# 24Vto5Vat1A-R1.net
KiCad netlist of a schematic drawn in Altium Designer
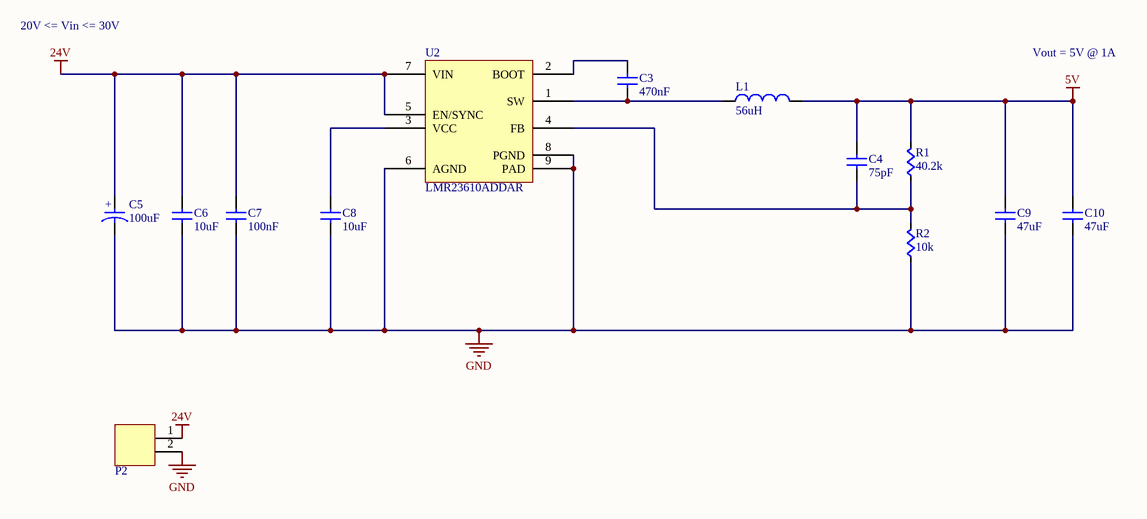
[diagram p0: 24Vto5Vat1A-R1.SchDoc]

(export (version "E")
  (design (tool "Eeschema 10.0.6"))
  (components
    (comp (ref "C3")
      (value "470nF")
      (footprint "CAPC0603")
      (fields (field (name "Comment") "Cap"))
      (libsource (lib "Passives") (part "Cap"))
    )
    (comp (ref "C4")
      (value "75pF")
      (footprint "CAPC0603")
      (fields (field (name "Comment") "Cap"))
      (libsource (lib "Passives") (part "Cap"))
    )
    (comp (ref "C5")
      (value "100uF")
      (footprint "EEHZA1H101P")
      (description "CAP ALUM POLY HYB 100UF 50V SMD")
      (fields (field (name "VOLTAGE") "50V") (field (name "TOLERANCE") "20%"))
      (libsource (lib "SubjuGator8") (part "EEHZA1H101P"))
    )
    (comp (ref "C6")
      (value "10uF")
      (footprint "CAP1210")
      (fields (field (name "Comment") "Cap"))
      (libsource (lib "Passives") (part "Cap"))
    )
    (comp (ref "C7")
      (value "100nF")
      (footprint "CAPC0603")
      (fields (field (name "Comment") "Cap"))
      (libsource (lib "Passives") (part "Cap"))
    )
    (comp (ref "C8")
      (value "10uF")
      (footprint "CAPC0603")
      (fields (field (name "Comment") "Cap"))
      (libsource (lib "Passives") (part "Cap"))
    )
    (comp (ref "C9")
      (value "47uF")
      (footprint "CAP1210")
      (fields (field (name "Comment") "Cap"))
      (libsource (lib "SubjuGator8") (part "Cap"))
    )
    (comp (ref "C10")
      (value "47uF")
      (footprint "CAP1210")
      (fields (field (name "Comment") "Cap"))
      (libsource (lib "SubjuGator8") (part "Cap"))
    )
    (comp (ref "L1")
      (value "56uH")
      (footprint "MSS1048-563MLB")
      (description "FIXED IND 56UH 1.7A 126 MOHM")
      (fields (field (name "Comment") "MSS1048-563MLB"))
      (libsource (lib "SubjuGator8") (part "MSS1048-563MLB"))
    )
    (comp (ref "P2")
      (value "2-pin Horz Sherlock")
      (footprint "MOLEX-HDR-1X2-SHERLOCK-HORZ")
      (fields
        (field (name "MANUFACTURER PART NUMBER") "0353630260")
        (field (name "MANUFACTURER") "Molex Inc")
      )
      (libsource (lib "SubjuGator8") (part "MOLEX-HDR-1x2-SHERLOCK_RA"))
    )
    (comp (ref "R1")
      (value "40.2k")
      (footprint "RES0603")
      (fields (field (name "Comment") "Res"))
      (libsource (lib "SubjuGator8") (part "Res"))
    )
    (comp (ref "R2")
      (value "10k")
      (footprint "RES0603")
      (fields (field (name "Comment") "Res"))
      (libsource (lib "SubjuGator8") (part "Res"))
    )
    (comp (ref "U2")
      (value "LMR23610ADDAR")
      (footprint "LMR23610ADDAR")
      (description "IC REG BUCK ADJ 1A SYNC 8SOPWRPD")
      (libsource (lib "SubjuGator8") (part "LMR23610ADDAR"))
    )
  )
  (nets
    (net (code "1") (name "5V") (class "Default")
      (node (ref "C10") (pin "1") (pinfunction "A_1") (pintype "passive"))
      (node (ref "C4") (pin "1") (pinfunction "A_1") (pintype "passive"))
      (node (ref "C9") (pin "1") (pinfunction "A_1") (pintype "passive"))
      (node (ref "L1") (pin "2") (pinfunction "2_2") (pintype "passive"))
      (node (ref "R1") (pin "1") (pinfunction "A_1") (pintype "passive"))
    )
    (net (code "2") (name "24V") (class "Default")
      (node (ref "C5") (pin "1") (pinfunction "1_1") (pintype "passive"))
      (node (ref "C6") (pin "1") (pinfunction "A_1") (pintype "passive"))
      (node (ref "C7") (pin "1") (pinfunction "A_1") (pintype "passive"))
      (node (ref "P2") (pin "1") (pinfunction "1_1") (pintype "passive"))
      (node (ref "U2") (pin "5") (pinfunction "EN/SYNC_5") (pintype "passive"))
      (node (ref "U2") (pin "7") (pinfunction "VIN_7") (pintype "passive"))
    )
    (net (code "3") (name "GND") (class "Default")
      (node (ref "C10") (pin "2") (pinfunction "B_2") (pintype "passive"))
      (node (ref "C5") (pin "2") (pinfunction "2_2") (pintype "passive"))
      (node (ref "C6") (pin "2") (pinfunction "B_2") (pintype "passive"))
      (node (ref "C7") (pin "2") (pinfunction "B_2") (pintype "passive"))
      (node (ref "C8") (pin "2") (pinfunction "B_2") (pintype "passive"))
      (node (ref "C9") (pin "2") (pinfunction "B_2") (pintype "passive"))
      (node (ref "P2") (pin "2") (pinfunction "2_2") (pintype "passive"))
      (node (ref "R2") (pin "2") (pinfunction "B_2") (pintype "passive"))
      (node (ref "U2") (pin "6") (pinfunction "AGND_6") (pintype "passive"))
      (node (ref "U2") (pin "8") (pinfunction "PGND_8") (pintype "passive"))
      (node (ref "U2") (pin "9") (pinfunction "PAD_9") (pintype "passive"))
    )
    (net (code "4") (name "Net-(C3-A)") (class "Default")
      (node (ref "C3") (pin "1") (pinfunction "A_1") (pintype "passive"))
      (node (ref "U2") (pin "2") (pinfunction "BOOT_2") (pintype "passive"))
    )
    (net (code "5") (name "Net-(C3-B)") (class "Default")
      (node (ref "C3") (pin "2") (pinfunction "B_2") (pintype "passive"))
      (node (ref "L1") (pin "1") (pinfunction "1_1") (pintype "passive"))
      (node (ref "U2") (pin "1") (pinfunction "SW_1") (pintype "passive"))
    )
    (net (code "6") (name "Net-(C4-B)") (class "Default")
      (node (ref "C4") (pin "2") (pinfunction "B_2") (pintype "passive"))
      (node (ref "R1") (pin "2") (pinfunction "B_2") (pintype "passive"))
      (node (ref "R2") (pin "1") (pinfunction "A_1") (pintype "passive"))
      (node (ref "U2") (pin "4") (pinfunction "FB_4") (pintype "passive"))
    )
    (net (code "7") (name "Net-(C8-A)") (class "Default")
      (node (ref "C8") (pin "1") (pinfunction "A_1") (pintype "passive"))
      (node (ref "U2") (pin "3") (pinfunction "VCC_3") (pintype "passive"))
    )
  )
)
